# TFTbarebones.net
KiCad netlist of a schematic drawn in EAGLE
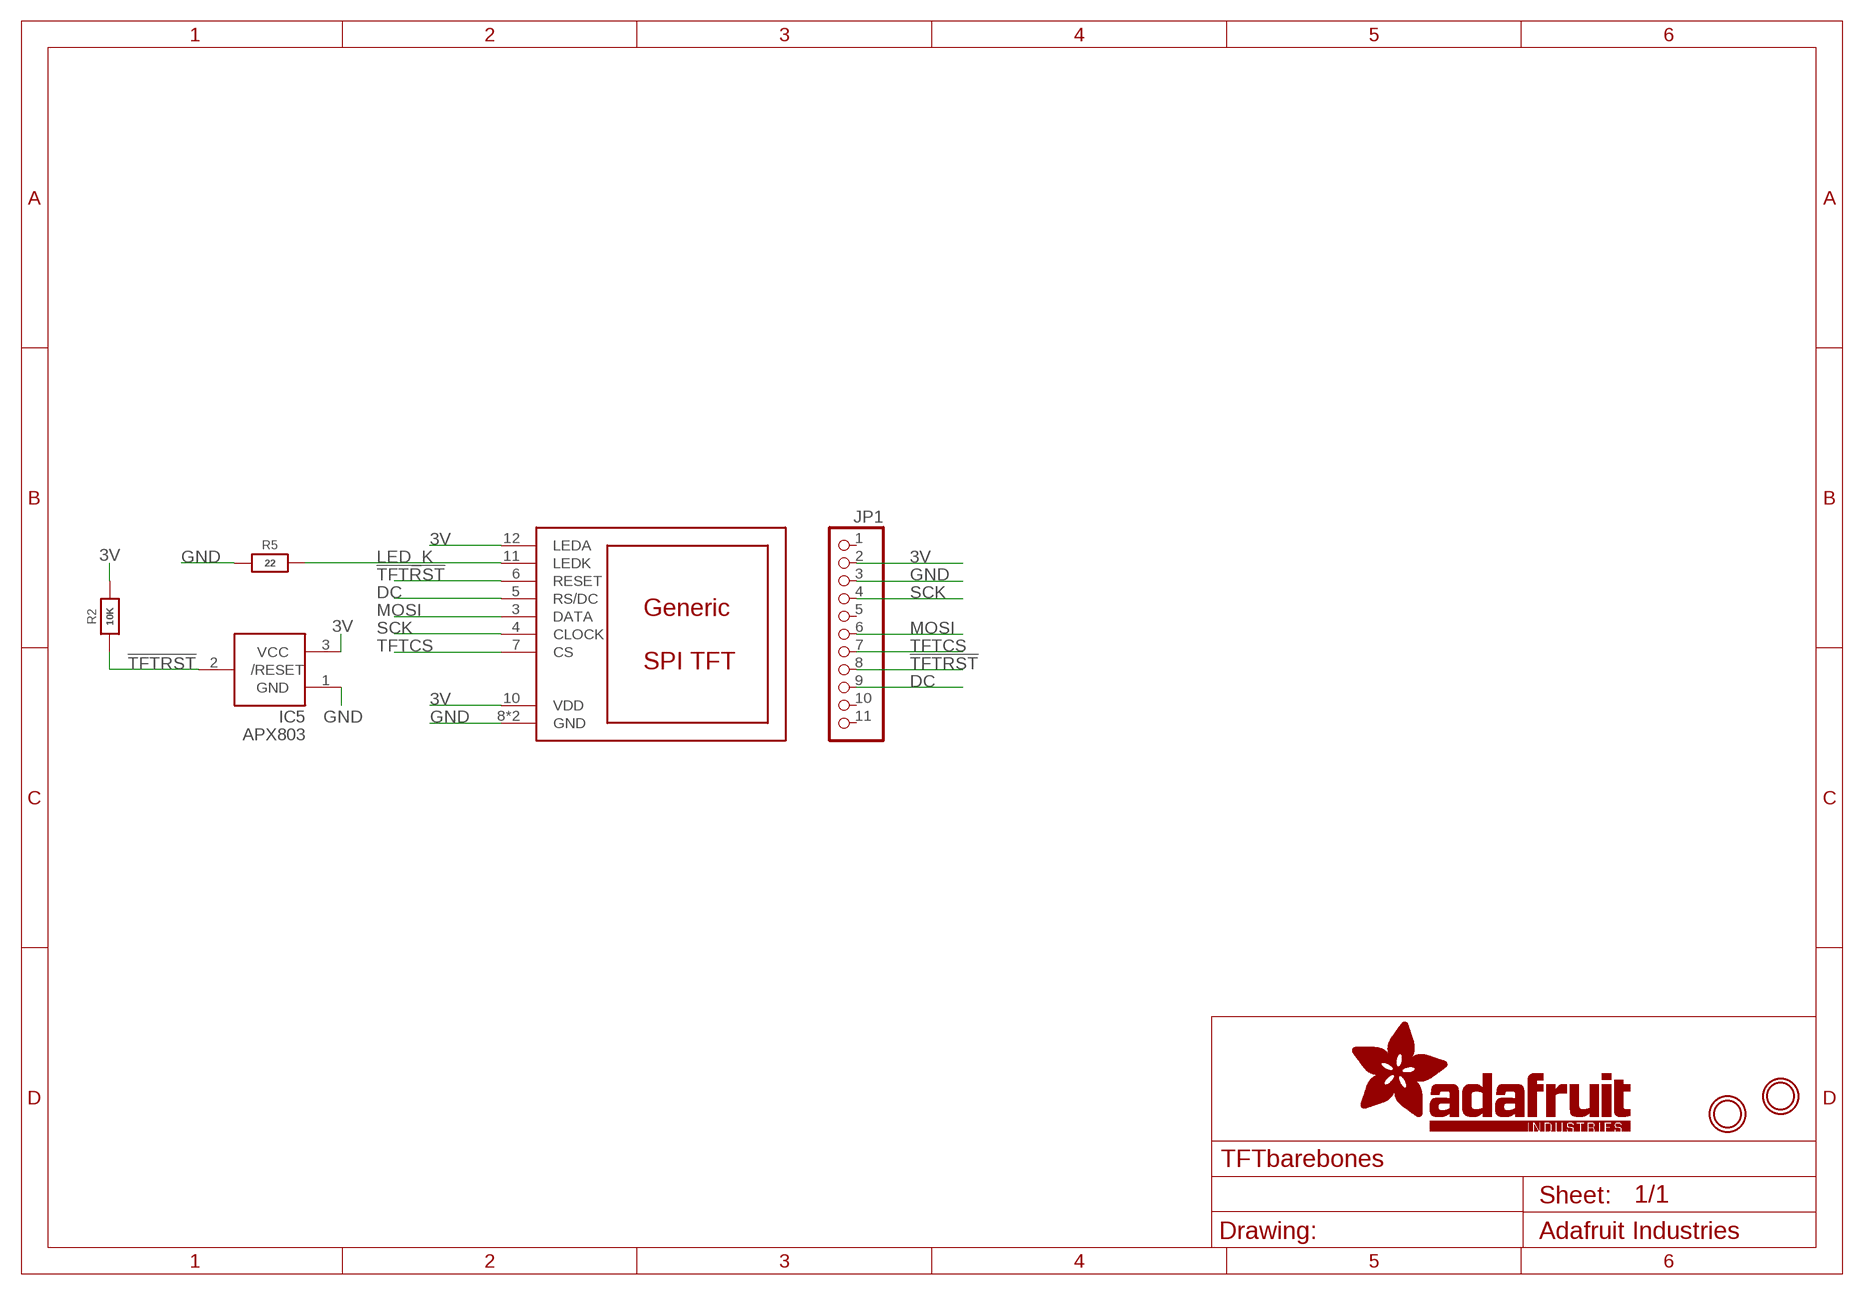
[diagram p0: schematic, sheet 1]

(export (version "E")
  (design (tool "Eeschema 10.0.6"))
  (components
    (comp (ref "DISP1")
      (value "DISP_LCD_GENERIC_SPI_1.14IN_240X135_WRAPUNDER")
      (footprint "eagle-import:TFT_1.14IN_240X135_WRAPUNDER")
      (libsource (lib "eagle-import") (part "DISP_LCD_GENERIC_SPI_1.14IN_240X135_WRAPUNDER"))
    )
    (comp (ref "IC5")
      (value "APX803")
      (footprint "eagle-import:SOT23")
      (libsource (lib "eagle-import") (part "AXP083-SAG"))
    )
    (comp (ref "JP1")
      (value "HEADER-1X11")
      (footprint "eagle-import:1X11_ROUND")
      (libsource (lib "eagle-import") (part "HEADER-1X11"))
    )
    (comp (ref "R2")
      (value "10K")
      (footprint "eagle-import:0603-NO")
      (libsource (lib "eagle-import") (part "RESISTOR_0603_NOOUT"))
    )
    (comp (ref "R5")
      (value "22")
      (footprint "eagle-import:0603-NO")
      (libsource (lib "eagle-import") (part "RESISTOR_0603_NOOUT"))
    )
    (comp (ref "U$9")
      (value "MOUNTINGHOLE2.5")
      (footprint "eagle-import:MOUNTINGHOLE_2.5_PLATED")
      (libsource (lib "eagle-import") (part "MOUNTINGHOLE2.5"))
    )
    (comp (ref "U$10")
      (value "MOUNTINGHOLE2.5")
      (footprint "eagle-import:MOUNTINGHOLE_2.5_PLATED")
      (libsource (lib "eagle-import") (part "MOUNTINGHOLE2.5"))
    )
  )
  (nets
    (net (code "1") (name "/3V") (class "Default")
      (node (ref "DISP1") (pin "10") (pinfunction "VDD_10") (pintype "power_in"))
      (node (ref "DISP1") (pin "12") (pinfunction "LEDA_12") (pintype "input"))
      (node (ref "IC5") (pin "3") (pinfunction "VCC_3") (pintype "power_in"))
      (node (ref "JP1") (pin "2") (pinfunction "2_2") (pintype "passive"))
      (node (ref "R2") (pin "2") (pinfunction "2_2") (pintype "passive"))
    )
    (net (code "2") (name "/DC") (class "Default")
      (node (ref "DISP1") (pin "5") (pinfunction "RS/DC_5") (pintype "input"))
      (node (ref "JP1") (pin "9") (pinfunction "9_9") (pintype "passive"))
    )
    (net (code "3") (name "/GND") (class "Default")
      (node (ref "DISP1") (pin "13") (pinfunction "GND_13") (pintype "power_in"))
      (node (ref "DISP1") (pin "8") (pinfunction "GND_8") (pintype "power_in"))
      (node (ref "IC5") (pin "1") (pinfunction "GND_1") (pintype "power_in"))
      (node (ref "JP1") (pin "3") (pinfunction "3_3") (pintype "passive"))
      (node (ref "R5") (pin "1") (pinfunction "1_1") (pintype "passive"))
    )
    (net (code "4") (name "/LED_K") (class "Default")
      (node (ref "DISP1") (pin "11") (pinfunction "LEDK_11") (pintype "input"))
      (node (ref "R5") (pin "2") (pinfunction "2_2") (pintype "passive"))
    )
    (net (code "5") (name "/MOSI") (class "Default")
      (node (ref "DISP1") (pin "3") (pinfunction "DATA_3") (pintype "bidirectional"))
      (node (ref "JP1") (pin "6") (pinfunction "6_6") (pintype "passive"))
    )
    (net (code "6") (name "/SCK") (class "Default")
      (node (ref "DISP1") (pin "4") (pinfunction "CLOCK_4") (pintype "input"))
      (node (ref "JP1") (pin "4") (pinfunction "4_4") (pintype "passive"))
    )
    (net (code "7") (name "/TFTCS") (class "Default")
      (node (ref "DISP1") (pin "7") (pinfunction "CS_7") (pintype "input"))
      (node (ref "JP1") (pin "7") (pinfunction "7_7") (pintype "passive"))
    )
    (net (code "8") (name "/~{TFTRST}") (class "Default")
      (node (ref "DISP1") (pin "6") (pinfunction "RESET_6") (pintype "input"))
      (node (ref "IC5") (pin "2") (pinfunction "/RESET_2") (pintype "output"))
      (node (ref "JP1") (pin "8") (pinfunction "8_8") (pintype "passive"))
      (node (ref "R2") (pin "1") (pinfunction "1_1") (pintype "passive"))
    )
    (net (code "9") (name "unconnected-(JP1-Pad1)") (class "Default")
      (node (ref "JP1") (pin "1") (pinfunction "1_1") (pintype "passive"))
    )
    (net (code "10") (name "unconnected-(JP1-Pad5)") (class "Default")
      (node (ref "JP1") (pin "5") (pinfunction "5_5") (pintype "passive"))
    )
    (net (code "11") (name "unconnected-(JP1-Pad10)") (class "Default")
      (node (ref "JP1") (pin "10") (pinfunction "10_10") (pintype "passive"))
    )
    (net (code "12") (name "unconnected-(JP1-Pad11)") (class "Default")
      (node (ref "JP1") (pin "11") (pinfunction "11_11") (pintype "passive"))
    )
  )
)
